# usb-debug.net
KiCad netlist of a schematic drawn in Altium Designer
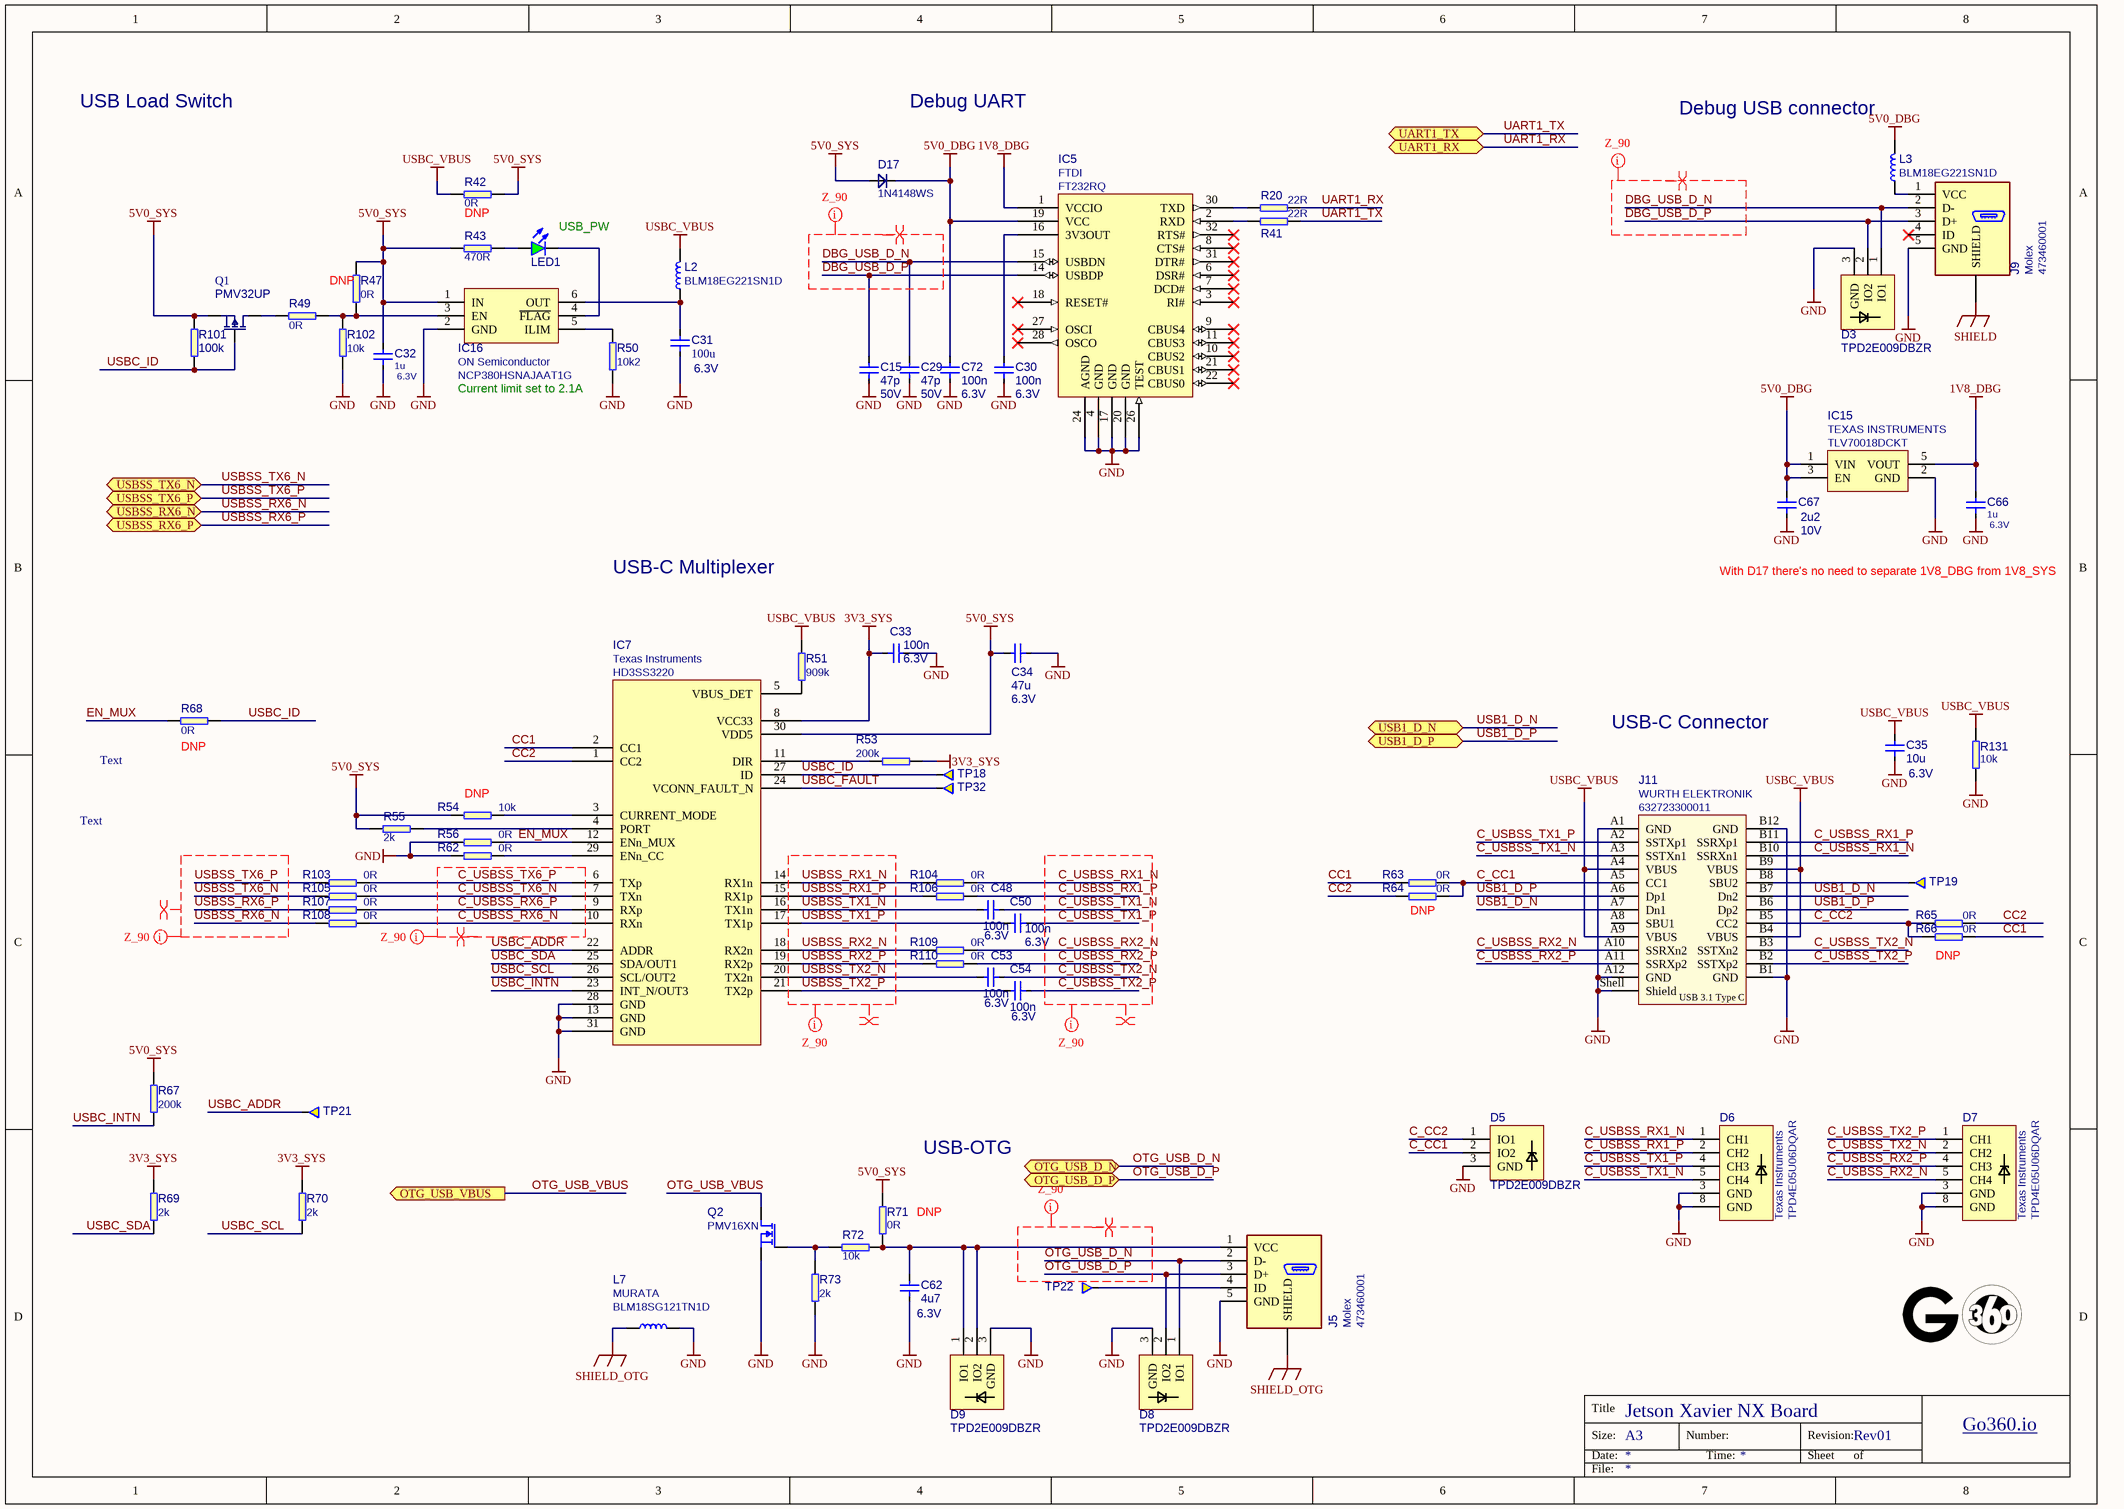
[diagram p0: usb-debug.SchDoc]

(export (version "E")
  (design (tool "Eeschema 10.0.6"))
  (components
    (comp (ref "C15")
      (value "47p")
      (footprint "0402")
      (description "MLCC SMT Capacitor 47pF 0402")
      (fields
        (field (name "PARTNUMBER") "C_47p_0402")
        (field (name "MANUFACTURER") "KEMET")
        (field (name "VOLTAGE") "50V")
      )
      (libsource (lib "jetson-nano-baseboard") (part "C_47p_0402"))
    )
    (comp (ref "C29")
      (value "47p")
      (footprint "0402")
      (description "MLCC SMT Capacitor 47pF 0402")
      (fields
        (field (name "PARTNUMBER") "C_47p_0402")
        (field (name "MANUFACTURER") "KEMET")
        (field (name "VOLTAGE") "50V")
      )
      (libsource (lib "jetson-nano-baseboard") (part "C_47p_0402"))
    )
    (comp (ref "C30")
      (value "100n")
      (footprint "0402")
      (description "MLCC SMT Capacitor 100n 0402")
      (fields
        (field (name "MANUFACTURER") "TDK")
        (field (name "PARTNUMBER") "C_100n_0402")
        (field (name "VOLTAGE") "6.3V")
      )
      (libsource (lib "jetson-nano-baseboard") (part "C_100n_0402"))
    )
    (comp (ref "C31")
      (value "100u")
      (footprint "1206")
      (description "MLCC SMT Capacitor 100uF 1206")
      (fields
        (field (name "PARTNUMBER") "C_100u_1206")
        (field (name "MANUFACTURER") "KEMET")
        (field (name "VOLTAGE") "6.3V")
      )
      (libsource (lib "jetson-nano-baseboard") (part "C_100u_1206"))
    )
    (comp (ref "C32")
      (value "1u")
      (footprint "0402")
      (description "MLCC SMT Capacitor 1uF 0402")
      (fields
        (field (name "PARTNUMBER") "C_1u_0402")
        (field (name "MANUFACTURER") "MULTICOMP")
        (field (name "VOLTAGE") "6.3V")
      )
      (libsource (lib "jetson-nano-baseboard") (part "C_1u_0402"))
    )
    (comp (ref "C33")
      (value "100n")
      (footprint "0402")
      (description "MLCC SMT Capacitor 100n 0402")
      (fields
        (field (name "MANUFACTURER") "TDK")
        (field (name "PARTNUMBER") "C_100n_0402")
        (field (name "VOLTAGE") "6.3V")
      )
      (libsource (lib "jetson-nano-baseboard") (part "C_100n_0402"))
    )
    (comp (ref "C34")
      (value "47u")
      (footprint "0805")
      (description "MLCC SMT Capacitor 47uF 0805")
      (fields
        (field (name "PARTNUMBER") "C_47u_0805")
        (field (name "MANUFACTURER") "KEMET")
        (field (name "VOLTAGE") "6.3V")
      )
      (libsource (lib "jetson-nano-baseboard") (part "C_47u_0805"))
    )
    (comp (ref "C35")
      (value "10u")
      (footprint "0603")
      (description "MLCC SMT Capacitor 10uF 0603")
      (fields
        (field (name "PARTNUMBER") "C_10u_0603")
        (field (name "MANUFACTURER") "Walsin")
        (field (name "VOLTAGE") "6.3V")
      )
      (libsource (lib "jetson-nano-baseboard") (part "C_10u_0603"))
    )
    (comp (ref "C48")
      (value "100n")
      (footprint "0402")
      (description "MLCC SMT Capacitor 100n 0402")
      (fields
        (field (name "MANUFACTURER") "TDK")
        (field (name "PARTNUMBER") "C_100n_0402")
        (field (name "VOLTAGE") "6.3V")
      )
      (libsource (lib "jetson-nano-baseboard") (part "C_100n_0402"))
    )
    (comp (ref "C50")
      (value "100n")
      (footprint "0402")
      (description "MLCC SMT Capacitor 100n 0402")
      (fields
        (field (name "MANUFACTURER") "TDK")
        (field (name "PARTNUMBER") "C_100n_0402")
        (field (name "VOLTAGE") "6.3V")
      )
      (libsource (lib "jetson-nano-baseboard") (part "C_100n_0402"))
    )
    (comp (ref "C53")
      (value "100n")
      (footprint "0402")
      (description "MLCC SMT Capacitor 100n 0402")
      (fields
        (field (name "MANUFACTURER") "TDK")
        (field (name "PARTNUMBER") "C_100n_0402")
        (field (name "VOLTAGE") "6.3V")
      )
      (libsource (lib "jetson-nano-baseboard") (part "C_100n_0402"))
    )
    (comp (ref "C54")
      (value "100n")
      (footprint "0402")
      (description "MLCC SMT Capacitor 100n 0402")
      (fields
        (field (name "MANUFACTURER") "TDK")
        (field (name "PARTNUMBER") "C_100n_0402")
        (field (name "VOLTAGE") "6.3V")
      )
      (libsource (lib "jetson-nano-baseboard") (part "C_100n_0402"))
    )
    (comp (ref "C62")
      (value "4u7")
      (footprint "0402")
      (description "MLCC SMT Capacitor 4.7uF 0402")
      (fields
        (field (name "PARTNUMBER") "C_4u7_0402")
        (field (name "MANUFACTURER") "MURATA")
        (field (name "VOLTAGE") "6.3V")
      )
      (libsource (lib "jetson-nano-baseboard") (part "C_4u7_0402"))
    )
    (comp (ref "C66")
      (value "1u")
      (footprint "0402")
      (description "MLCC SMT Capacitor 1uF 0402")
      (fields
        (field (name "PARTNUMBER") "C_1u_0402")
        (field (name "MANUFACTURER") "MULTICOMP")
        (field (name "VOLTAGE") "6.3V")
      )
      (libsource (lib "jetson-nano-baseboard") (part "C_1u_0402"))
    )
    (comp (ref "C67")
      (value "2u2")
      (footprint "0402")
      (description "MLCC SMT Capacitor 2.2uF 0402")
      (fields
        (field (name "MANUFACTURER") "TDK")
        (field (name "PARTNUMBER") "C_2u2_0402")
        (field (name "VOLTAGE") "10V")
      )
      (libsource (lib "jetson-nano-baseboard") (part "C_2u2_0402"))
    )
    (comp (ref "C72")
      (value "100n")
      (footprint "0402")
      (description "MLCC SMT Capacitor 100n 0402")
      (fields
        (field (name "MANUFACTURER") "TDK")
        (field (name "PARTNUMBER") "C_100n_0402")
        (field (name "VOLTAGE") "6.3V")
      )
      (libsource (lib "jetson-nano-baseboard") (part "C_100n_0402"))
    )
    (comp (ref "D3")
      (value "TPD2E009DBZR")
      (footprint "SOT-23")
      (description "DIODE, SCHOTTKY, 30V, 200MA, SOT-23")
      (fields (field (name "MANUFACTURER") "NXP"))
      (libsource (lib "jetson-nano-baseboard") (part "TPD2E009DBZR"))
    )
    (comp (ref "D5")
      (value "TPD2E009DBZR")
      (footprint "SOT-23")
      (description "DIODE, SCHOTTKY, 30V, 200MA, SOT-23")
      (fields (field (name "MANUFACTURER") "NXP"))
      (libsource (lib "") (part "TPD2E009DBZR_2"))
    )
    (comp (ref "D6")
      (value "TPD4E05U06")
      (footprint "TPD4E05U06_PASS")
      (description "ESD Suppressors 4-CH")
      (fields
        (field (name "PARTNUMBER") "TPD4E05U06_PASS")
        (field (name "MANUFACTURER") "Texas Instruments")
        (field (name "PARTSYMBOL") "TPD4E05U06DQAR")
      )
      (libsource (lib "jetson-nano-baseboard") (part "TPD4E05U06"))
    )
    (comp (ref "D7")
      (value "TPD4E05U06")
      (footprint "TPD4E05U06_PASS")
      (description "ESD Suppressors 4-CH")
      (fields
        (field (name "PARTNUMBER") "TPD4E05U06_PASS")
        (field (name "MANUFACTURER") "Texas Instruments")
        (field (name "PARTSYMBOL") "TPD4E05U06DQAR")
      )
      (libsource (lib "jetson-nano-baseboard") (part "TPD4E05U06"))
    )
    (comp (ref "D8")
      (value "TPD2E009DBZR")
      (footprint "SOT-23s")
      (description "DIODE, SCHOTTKY, 30V, 200MA, SOT-23")
      (fields (field (name "MANUFACTURER") "NXP"))
      (libsource (lib "jetson-nano-baseboard") (part "TPD2E009DBZR"))
    )
    (comp (ref "D9")
      (value "TPD2E009DBZR")
      (footprint "SOT-23s")
      (description "DIODE, SCHOTTKY, 30V, 200MA, SOT-23")
      (fields (field (name "MANUFACTURER") "NXP"))
      (libsource (lib "") (part "TPD2E009DBZR_1"))
    )
    (comp (ref "D17")
      (value "1N4148WS")
      (footprint "SOD-323")
      (description "Diode small signal")
      (fields (field (name "MANUFACTURER") "ON SEMICONDUCTOR"))
      (libsource (lib "jetson-nano-baseboard") (part "diode"))
    )
    (comp (ref "IC5")
      (value "FT232RQ")
      (footprint "QFN-32")
      (description "USB to serial UART interface")
      (fields (field (name "MANUFACTURER") "FTDI") (field (name "PARTNUMBER") "FT232RQ"))
      (libsource (lib "jetson-nano-baseboard") (part "FT232RQ"))
    )
    (comp (ref "IC7")
      (value "HD3SS3220")
      (footprint "RNH0030A")
      (description "IC DRP PORT CTLR USB-C 30WQFN")
      (fields (field (name "MANUFACTURER") "Texas Instruments"))
      (libsource (lib "jetson-nano-baseboard") (part "HD3SS3220"))
    )
    (comp (ref "IC15")
      (value "TLV70018DCKT")
      (footprint "SC70-5")
      (description "Voltage Regulator, 2V to 5.5V, 175mV Dropout, 1.8Vout, 200mAout")
      (fields (field (name "MANUFACTURER") "TEXAS INSTRUMENTS"))
      (libsource (lib "jetson-nano-baseboard") (part "TLV700"))
    )
    (comp (ref "IC16")
      (value "NCP380HSNAJAAT1G")
      (footprint "TSOP-6")
      (description "POWER LOAD SWITCH, HIGH SIDE")
      (fields (field (name "MANUFACTURER") "ON Semiconductor"))
      (libsource (lib "jetson-nano-baseboard") (part "NCP380HSNAJAAT1G"))
    )
    (comp (ref "J5")
      (value "Molex 47346-0001")
      (footprint "CON-Molex-047346-0001")
      (description "USB - micro B Receptacle Connector 5 Position Surface Mount, Right Angle, Horizontal")
      (fields
        (field (name "PARTNUMBER") "CON-Molex-47346-0001")
        (field (name "MANUFACTURER") "Molex")
        (field (name "PARTSYMBOL") "473460001")
      )
      (libsource (lib "jetson-nano-baseboard") (part "Micro USB B"))
    )
    (comp (ref "J9")
      (value "Molex 47346-0001")
      (footprint "CON-Molex-047346-0001")
      (description "USB - micro B Receptacle Connector 5 Position Surface Mount, Right Angle, Horizontal")
      (fields
        (field (name "PARTNUMBER") "CON-Molex-47346-0001")
        (field (name "MANUFACTURER") "Molex")
        (field (name "PARTSYMBOL") "473460001")
      )
      (libsource (lib "jetson-nano-baseboard") (part "Micro USB B"))
    )
    (comp (ref "J11")
      (value "632723300011")
      (footprint "WE_632723300011")
      (description "USB 3.1 Type C Receptacle Horizontal THR WR-COM")
      (fields (field (name "PARTNUMBER") "WE_632723300011") (field (name "MANUFACTURER") "WURTH ELEKTRONIK"))
      (libsource (lib "jetson-nano-baseboard") (part "WE_632723300011"))
    )
    (comp (ref "L2")
      (value "BLM18EG221SN1D")
      (footprint "0603")
      (description "MURATA  BLM18EG221SN1D  FERRITE BEAD, 0.05OHM, 2A, 0603")
      (fields (field (name "MANUFACTURER") "MURATA"))
      (libsource (lib "jetson-nano-baseboard") (part "BLM18EG221SN1D"))
    )
    (comp (ref "L3")
      (value "BLM18EG221SN1D")
      (footprint "0603")
      (description "MURATA  BLM18EG221SN1D  FERRITE BEAD, 0.05OHM, 2A, 0603")
      (fields (field (name "MANUFACTURER") "MURATA"))
      (libsource (lib "jetson-nano-baseboard") (part "BLM18EG221SN1D"))
    )
    (comp (ref "L7")
      (value "BLM18SG121TN1D")
      (footprint "0603")
      (description "FERRITE BEAD, 0.025OHM, 3A, 0603")
      (fields (field (name "MANUFACTURER") "MURATA"))
      (libsource (lib "jetson-nano-baseboard") (part "BLM18SG121TN1D"))
    )
    (comp (ref "LED1")
      (value "KPT-1608SGC")
      (footprint "LED0603")
      (description "LED Green 0603 case")
      (fields (field (name "MANUFACTURER") "KINGBRIGHT") (field (name "PARTNUMBER") "LED_G"))
      (libsource (lib "jetson-nano-baseboard") (part "LED"))
    )
    (comp (ref "Q1")
      (value "PMV32UP")
      (footprint "SOT-23s")
      (description "P CH, 20V, 4A")
      (fields (field (name "MANUFACTURER") "NXP"))
      (libsource (lib "jetson-nano-baseboard") (part "PMOS"))
    )
    (comp (ref "Q2")
      (value "PMV16XN")
      (footprint "SOT-23s")
      (description "MOSFET, N CH")
      (fields (field (name "MANUFACTURER") "NXP"))
      (libsource (lib "jetson-nano-baseboard") (part "NMOS_PMV16XN"))
    )
    (comp (ref "R20")
      (value "22R")
      (footprint "0402")
      (description "RES, 22R, 0402")
      (fields (field (name "MANUFACTURER") "VISHAY") (field (name "PARTNUMBER") "R_22R_0402"))
      (libsource (lib "jetson-nano-baseboard") (part "R_22R_0402"))
    )
    (comp (ref "R41")
      (value "22R")
      (footprint "0402")
      (description "RES, 22R, 0402")
      (fields (field (name "MANUFACTURER") "VISHAY") (field (name "PARTNUMBER") "R_22R_0402"))
      (libsource (lib "jetson-nano-baseboard") (part "R_22R_0402"))
    )
    (comp (ref "R42")
      (value "0R")
      (footprint "0402")
      (description "RES, 0R, 0402")
      (fields (field (name "PARTNUMBER") "R_0R_0402") (field (name "MANUFACTURER") "Panasonic"))
      (libsource (lib "") (part "R_0R_0402_2"))
    )
    (comp (ref "R43")
      (value "470R")
      (footprint "0402")
      (description "RES, 470R, 0402")
      (fields (field (name "PARTNUMBER") "R_470R_0402") (field (name "MANUFACTURER") "VISHAY"))
      (libsource (lib "jetson-nano-baseboard") (part "R_470R_0402"))
    )
    (comp (ref "R47")
      (value "0R")
      (footprint "0402")
      (description "RES, 0R, 0402")
      (fields (field (name "PARTNUMBER") "R_0R_0402") (field (name "MANUFACTURER") "Panasonic"))
      (libsource (lib "") (part "R_0R_0402_1"))
    )
    (comp (ref "R49")
      (value "0R")
      (footprint "0402")
      (description "RES, 0R, 0402")
      (fields (field (name "PARTNUMBER") "R_0R_0402") (field (name "MANUFACTURER") "Panasonic"))
      (libsource (lib "jetson-nano-baseboard") (part "R_0R_0402"))
    )
    (comp (ref "R50")
      (value "10k2")
      (footprint "0402")
      (description "RES, 10k2, 0402, 0.1%")
      (fields (field (name "PARTNUMBER") "R_10k2_0402_0.1%") (field (name "MANUFACTURER") "TE CONECTIVITY"))
      (libsource (lib "jetson-nano-baseboard") (part "R_10k2_0402"))
    )
    (comp (ref "R51")
      (value "909k")
      (footprint "0402")
      (description "RES, 909k, 0402")
      (fields (field (name "PARTNUMBER") "R_909k_0402") (field (name "MANUFACTURER") "Panasonic"))
      (libsource (lib "jetson-nano-baseboard") (part "R_909k_0402"))
    )
    (comp (ref "R53")
      (value "200k")
      (footprint "0402")
      (description "RES, 200k, 0402")
      (fields (field (name "PARTNUMBER") "R_200k_0402") (field (name "MANUFACTURER") "YAGEO"))
      (libsource (lib "jetson-nano-baseboard") (part "R_200k_0402"))
    )
    (comp (ref "R54")
      (value "10k")
      (footprint "0402")
      (description "RES, 10k, 0402")
      (fields (field (name "PARTNUMBER") "R_10k_0402") (field (name "MANUFACTURER") "MULTICOMP"))
      (libsource (lib "jetson-nano-baseboard") (part "R_10k_0402"))
    )
    (comp (ref "R55")
      (value "2k")
      (footprint "0402")
      (description "RES, 2k, 0402")
      (fields (field (name "PARTNUMBER") "R_2k_0402") (field (name "MANUFACTURER") "VISHAY"))
      (libsource (lib "") (part "R_2k_0402_1"))
    )
    (comp (ref "R56")
      (value "0R")
      (footprint "0402")
      (description "RES, 0R, 0402")
      (fields (field (name "PARTNUMBER") "R_0R_0402") (field (name "MANUFACTURER") "Panasonic"))
      (libsource (lib "jetson-nano-baseboard") (part "R_0R_0402"))
    )
    (comp (ref "R62")
      (value "0R")
      (footprint "0402")
      (description "RES, 0R, 0402")
      (fields (field (name "PARTNUMBER") "R_0R_0402") (field (name "MANUFACTURER") "Panasonic"))
      (libsource (lib "jetson-nano-baseboard") (part "R_0R_0402"))
    )
    (comp (ref "R63")
      (value "0R")
      (footprint "0402")
      (description "RES, 0R, 0402")
      (fields (field (name "PARTNUMBER") "R_0R_0402") (field (name "MANUFACTURER") "Panasonic"))
      (libsource (lib "jetson-nano-baseboard") (part "R_0R_0402"))
    )
    (comp (ref "R64")
      (value "0R")
      (footprint "0402")
      (description "RES, 0R, 0402")
      (fields (field (name "PARTNUMBER") "R_0R_0402") (field (name "MANUFACTURER") "Panasonic"))
      (libsource (lib "jetson-nano-baseboard") (part "R_0R_0402"))
    )
    (comp (ref "R65")
      (value "0R")
      (footprint "0402")
      (description "RES, 0R, 0402")
      (fields (field (name "PARTNUMBER") "R_0R_0402") (field (name "MANUFACTURER") "Panasonic"))
      (libsource (lib "jetson-nano-baseboard") (part "R_0R_0402"))
    )
    (comp (ref "R66")
      (value "0R")
      (footprint "0402")
      (description "RES, 0R, 0402")
      (fields (field (name "PARTNUMBER") "R_0R_0402") (field (name "MANUFACTURER") "Panasonic"))
      (libsource (lib "jetson-nano-baseboard") (part "R_0R_0402"))
    )
    (comp (ref "R67")
      (value "200k")
      (footprint "0402")
      (description "RES, 200k, 0402")
      (fields (field (name "PARTNUMBER") "R_200k_0402") (field (name "MANUFACTURER") "YAGEO"))
      (libsource (lib "") (part "R_200k_0402_1"))
    )
    (comp (ref "R68")
      (value "0R")
      (footprint "0402")
      (description "RES, 0R, 0402")
      (fields (field (name "PARTNUMBER") "R_0R_0402") (field (name "MANUFACTURER") "Panasonic"))
      (libsource (lib "jetson-nano-baseboard") (part "R_0R_0402"))
    )
    (comp (ref "R69")
      (value "2k")
      (footprint "0402")
      (description "RES, 2k, 0402")
      (fields (field (name "PARTNUMBER") "R_2k_0402") (field (name "MANUFACTURER") "VISHAY"))
      (libsource (lib "jetson-nano-baseboard") (part "R_2k_0402"))
    )
    (comp (ref "R70")
      (value "2k")
      (footprint "0402")
      (description "RES, 2k, 0402")
      (fields (field (name "PARTNUMBER") "R_2k_0402") (field (name "MANUFACTURER") "VISHAY"))
      (libsource (lib "jetson-nano-baseboard") (part "R_2k_0402"))
    )
    (comp (ref "R71")
      (value "0R")
      (footprint "0402")
      (description "RES, 0R, 0402")
      (fields (field (name "PARTNUMBER") "R_0R_0402") (field (name "MANUFACTURER") "Panasonic"))
      (libsource (lib "jetson-nano-baseboard") (part "R_0R_0402"))
    )
    (comp (ref "R72")
      (value "10k")
      (footprint "0402")
      (description "RES, 10k, 0402")
      (fields (field (name "PARTNUMBER") "R_10k_0402") (field (name "MANUFACTURER") "MULTICOMP"))
      (libsource (lib "") (part "R_10k_0402_2"))
    )
    (comp (ref "R73")
      (value "2k")
      (footprint "0402")
      (description "RES, 2k, 0402")
      (fields (field (name "PARTNUMBER") "R_2k_0402") (field (name "MANUFACTURER") "VISHAY"))
      (libsource (lib "jetson-nano-baseboard") (part "R_2k_0402"))
    )
    (comp (ref "R101")
      (value "100k")
      (footprint "0402")
      (description "SMT Resistor 100k 0402")
      (fields (field (name "PARTNUMBER") "R_100k_0402") (field (name "TOLERANCE") "1%"))
      (libsource (lib "jetson-nano-baseboard") (part "R_100k_0402"))
    )
    (comp (ref "R102")
      (value "10k")
      (footprint "0402")
      (description "RES, 10k, 0402")
      (fields (field (name "MANUFACTURER") "MULTICOMP") (field (name "PARTNUMBER") "R_10k_0402"))
      (libsource (lib "") (part "R_10k_0402_1"))
    )
    (comp (ref "R103")
      (value "0R")
      (footprint "0402")
      (description "RES, 0R, 0402")
      (fields (field (name "PARTNUMBER") "R_0R_0402") (field (name "MANUFACTURER") "Panasonic"))
      (libsource (lib "jetson-nano-baseboard") (part "R_0R_0402"))
    )
    (comp (ref "R104")
      (value "0R")
      (footprint "0402")
      (description "RES, 0R, 0402")
      (fields (field (name "PARTNUMBER") "R_0R_0402") (field (name "MANUFACTURER") "Panasonic"))
      (libsource (lib "jetson-nano-baseboard") (part "R_0R_0402"))
    )
    (comp (ref "R105")
      (value "0R")
      (footprint "0402")
      (description "RES, 0R, 0402")
      (fields (field (name "PARTNUMBER") "R_0R_0402") (field (name "MANUFACTURER") "Panasonic"))
      (libsource (lib "jetson-nano-baseboard") (part "R_0R_0402"))
    )
    (comp (ref "R106")
      (value "0R")
      (footprint "0402")
      (description "RES, 0R, 0402")
      (fields (field (name "PARTNUMBER") "R_0R_0402") (field (name "MANUFACTURER") "Panasonic"))
      (libsource (lib "jetson-nano-baseboard") (part "R_0R_0402"))
    )
    (comp (ref "R107")
      (value "0R")
      (footprint "0402")
      (description "RES, 0R, 0402")
      (fields (field (name "PARTNUMBER") "R_0R_0402") (field (name "MANUFACTURER") "Panasonic"))
      (libsource (lib "jetson-nano-baseboard") (part "R_0R_0402"))
    )
    (comp (ref "R108")
      (value "0R")
      (footprint "0402")
      (description "RES, 0R, 0402")
      (fields (field (name "PARTNUMBER") "R_0R_0402") (field (name "MANUFACTURER") "Panasonic"))
      (libsource (lib "jetson-nano-baseboard") (part "R_0R_0402"))
    )
    (comp (ref "R109")
      (value "0R")
      (footprint "0402")
      (description "RES, 0R, 0402")
      (fields (field (name "PARTNUMBER") "R_0R_0402") (field (name "MANUFACTURER") "Panasonic"))
      (libsource (lib "jetson-nano-baseboard") (part "R_0R_0402"))
    )
    (comp (ref "R110")
      (value "0R")
      (footprint "0402")
      (description "RES, 0R, 0402")
      (fields (field (name "PARTNUMBER") "R_0R_0402") (field (name "MANUFACTURER") "Panasonic"))
      (libsource (lib "jetson-nano-baseboard") (part "R_0R_0402"))
    )
    (comp (ref "R131")
      (value "10k")
      (footprint "0402")
      (description "RES, 10k, 0402")
      (fields (field (name "PARTNUMBER") "R_10k_0402") (field (name "MANUFACTURER") "MULTICOMP"))
      (libsource (lib "") (part "R_10k_0402_1"))
    )
    (comp (ref "TP18")
      (value "Testpad")
      (footprint "TP-R-1.5")
      (description "Testpad, round, 1.5mm")
      (fields (field (name "PARTNUMBER") "TP-R-1.5"))
      (libsource (lib "jetson-nano-baseboard") (part "Testpad"))
    )
    (comp (ref "TP19")
      (value "Testpad")
      (footprint "TP-R-1.5")
      (description "Testpad, round, 1.5mm")
      (fields (field (name "PARTNUMBER") "TP-R-1.5"))
      (libsource (lib "jetson-nano-baseboard") (part "Testpad"))
    )
    (comp (ref "TP21")
      (value "Testpad")
      (footprint "TP-R-1.5")
      (description "Testpad, round, 1.5mm")
      (fields (field (name "PARTNUMBER") "TP-R-1.5"))
      (libsource (lib "jetson-nano-baseboard") (part "Testpad"))
    )
    (comp (ref "TP22")
      (value "Testpad")
      (footprint "TP-R-1.5")
      (description "Testpad, round, 1.5mm")
      (fields (field (name "PARTNUMBER") "TP-R-1.5"))
      (libsource (lib "jetson-nano-baseboard") (part "Testpad"))
    )
    (comp (ref "TP32")
      (value "Testpad")
      (footprint "TP-R-1.5")
      (description "Testpad, round, 1.5mm")
      (fields (field (name "PARTNUMBER") "TP-R-1.5"))
      (libsource (lib "jetson-nano-baseboard") (part "Testpad"))
    )
  )
  (nets
    (net (code "1") (name "/CC1") (class "Default")
      (node (ref "IC7") (pin "2") (pinfunction "CC1_2") (pintype "passive"))
      (node (ref "R63") (pin "1") (pintype "passive"))
      (node (ref "R66") (pin "2") (pintype "passive"))
    )
    (net (code "2") (name "/CC2") (class "Default")
      (node (ref "IC7") (pin "1") (pinfunction "CC2_1") (pintype "passive"))
      (node (ref "R64") (pin "1") (pintype "passive"))
      (node (ref "R65") (pin "2") (pintype "passive"))
    )
    (net (code "3") (name "/C_CC1") (class "Default")
      (node (ref "D5") (pin "2") (pinfunction "IO2_2") (pintype "passive"))
      (node (ref "J11") (pin "A5") (pinfunction "CC1_A5") (pintype "passive"))
      (node (ref "R63") (pin "2") (pintype "passive"))
      (node (ref "R64") (pin "2") (pintype "passive"))
    )
    (net (code "4") (name "/C_CC2") (class "Default")
      (node (ref "D5") (pin "1") (pinfunction "IO1_1") (pintype "passive"))
      (node (ref "J11") (pin "B5") (pinfunction "CC2_B5") (pintype "passive"))
      (node (ref "R65") (pin "1") (pintype "passive"))
      (node (ref "R66") (pin "1") (pintype "passive"))
    )
    (net (code "5") (name "/C_USBSS_RX1_N") (class "Default")
      (node (ref "D6") (pin "1") (pinfunction "CH1_1") (pintype "passive"))
      (node (ref "J11") (pin "B10") (pinfunction "SSRXn1_B10") (pintype "passive"))
      (node (ref "R104") (pin "2") (pintype "passive"))
    )
    (net (code "6") (name "/C_USBSS_RX1_P") (class "Default")
      (node (ref "D6") (pin "2") (pinfunction "CH2_2") (pintype "passive"))
      (node (ref "J11") (pin "B11") (pinfunction "SSRXp1_B11") (pintype "passive"))
      (node (ref "R106") (pin "2") (pintype "passive"))
    )
    (net (code "7") (name "/C_USBSS_RX2_N") (class "Default")
      (node (ref "D7") (pin "5") (pinfunction "CH4_5") (pintype "passive"))
      (node (ref "J11") (pin "A10") (pinfunction "SSRXn2_A10") (pintype "passive"))
      (node (ref "R109") (pin "2") (pintype "passive"))
    )
    (net (code "8") (name "/C_USBSS_RX2_P") (class "Default")
      (node (ref "D7") (pin "4") (pinfunction "CH3_4") (pintype "passive"))
      (node (ref "J11") (pin "A11") (pinfunction "SSRXp2_A11") (pintype "passive"))
      (node (ref "R110") (pin "2") (pintype "passive"))
    )
    (net (code "9") (name "/C_USBSS_RX6_N") (class "Default")
      (node (ref "IC7") (pin "10") (pinfunction "RXn_10") (pintype "passive"))
      (node (ref "R108") (pin "2") (pintype "passive"))
    )
    (net (code "10") (name "/C_USBSS_RX6_P") (class "Default")
      (node (ref "IC7") (pin "9") (pinfunction "RXp_9") (pintype "passive"))
      (node (ref "R107") (pin "2") (pintype "passive"))
    )
    (net (code "11") (name "/C_USBSS_TX1_N") (class "Default")
      (node (ref "C48") (pin "1") (pinfunction "1_1") (pintype "passive"))
      (node (ref "D6") (pin "5") (pinfunction "CH4_5") (pintype "passive"))
      (node (ref "J11") (pin "A3") (pinfunction "SSTXn1_A3") (pintype "passive"))
    )
    (net (code "12") (name "/C_USBSS_TX1_P") (class "Default")
      (node (ref "C50") (pin "1") (pinfunction "1_1") (pintype "passive"))
      (node (ref "D6") (pin "4") (pinfunction "CH3_4") (pintype "passive"))
      (node (ref "J11") (pin "A2") (pinfunction "SSTXp1_A2") (pintype "passive"))
    )
    (net (code "13") (name "/C_USBSS_TX2_N") (class "Default")
      (node (ref "C53") (pin "1") (pinfunction "1_1") (pintype "passive"))
      (node (ref "D7") (pin "2") (pinfunction "CH2_2") (pintype "passive"))
      (node (ref "J11") (pin "B3") (pinfunction "SSTXn2_B3") (pintype "passive"))
    )
    (net (code "14") (name "/C_USBSS_TX2_P") (class "Default")
      (node (ref "C54") (pin "1") (pinfunction "1_1") (pintype "passive"))
      (node (ref "D7") (pin "1") (pinfunction "CH1_1") (pintype "passive"))
      (node (ref "J11") (pin "B2") (pinfunction "SSTXp2_B2") (pintype "passive"))
    )
    (net (code "15") (name "/C_USBSS_TX6_N") (class "Default")
      (node (ref "IC7") (pin "7") (pinfunction "TXn_7") (pintype "passive"))
      (node (ref "R105") (pin "2") (pintype "passive"))
    )
    (net (code "16") (name "/C_USBSS_TX6_P") (class "Default")
      (node (ref "IC7") (pin "6") (pinfunction "TXp_6") (pintype "passive"))
      (node (ref "R103") (pin "2") (pintype "passive"))
    )
    (net (code "17") (name "/DBG_USB_D_N") (class "Default")
      (node (ref "C29") (pin "2") (pinfunction "2_2") (pintype "passive"))
      (node (ref "D3") (pin "1") (pinfunction "IO1_1") (pintype "passive"))
      (node (ref "IC5") (pin "15") (pinfunction "USBDN_15") (pintype "bidirectional"))
      (node (ref "J9") (pin "2") (pinfunction "D-_2") (pintype "passive"))
    )
    (net (code "18") (name "/DBG_USB_D_P") (class "Default")
      (node (ref "C15") (pin "2") (pinfunction "2_2") (pintype "passive"))
      (node (ref "D3") (pin "2") (pinfunction "IO2_2") (pintype "passive"))
      (node (ref "IC5") (pin "14") (pinfunction "USBDP_14") (pintype "bidirectional"))
      (node (ref "J9") (pin "3") (pinfunction "D+_3") (pintype "passive"))
    )
    (net (code "19") (name "/EN_MUX") (class "Default")
      (node (ref "IC7") (pin "12") (pinfunction "ENn_MUX_12") (pintype "passive"))
      (node (ref "R56") (pin "2") (pintype "passive"))
      (node (ref "R68") (pin "1") (pintype "passive"))
    )
    (net (code "20") (name "/OTG_USB_D_N") (class "Default")
      (node (ref "D8") (pin "1") (pinfunction "IO1_1") (pintype "passive"))
      (node (ref "J5") (pin "2") (pinfunction "D-_2") (pintype "passive"))
    )
    (net (code "21") (name "/OTG_USB_D_P") (class "Default")
      (node (ref "D8") (pin "2") (pinfunction "IO2_2") (pintype "passive"))
      (node (ref "J5") (pin "3") (pinfunction "D+_3") (pintype "passive"))
    )
    (net (code "22") (name "/OTG_USB_VBUS") (class "Default")
      (node (ref "Q2") (pin "3") (pinfunction "D_3") (pintype "passive"))
    )
    (net (code "23") (name "/UART1_RX") (class "Default") (node (ref "R20") (pin "2") (pintype "passive")))
    (net (code "24") (name "/UART1_TX") (class "Default") (node (ref "R41") (pin "2") (pintype "passive")))
    (net (code "25") (name "/USB1_D_N") (class "Default")
      (node (ref "J11") (pin "A7") (pinfunction "Dn1_A7") (pintype "passive"))
      (node (ref "J11") (pin "B7") (pinfunction "Dn2_B7") (pintype "passive"))
    )
    (net (code "26") (name "/USB1_D_P") (class "Default")
      (node (ref "J11") (pin "A6") (pinfunction "Dp1_A6") (pintype "passive"))
      (node (ref "J11") (pin "B6") (pinfunction "Dp2_B6") (pintype "passive"))
    )
    (net (code "27") (name "/USBC_ADDR") (class "Default")
      (node (ref "IC7") (pin "22") (pinfunction "ADDR_22") (pintype "passive"))
      (node (ref "TP21") (pin "1") (pintype "passive"))
    )
    (net (code "28") (name "/USBC_FAULT") (class "Default")
      (node (ref "IC7") (pin "24") (pinfunction "VCONN_FAULT_N_24") (pintype "passive"))
      (node (ref "TP32") (pin "1") (pintype "passive"))
    )
    (net (code "29") (name "/USBC_ID") (class "Default")
      (node (ref "IC7") (pin "27") (pinfunction "ID_27") (pintype "passive"))
      (node (ref "Q1") (pin "1") (pinfunction "G_1") (pintype "passive"))
      (node (ref "R101") (pin "1") (pintype "passive"))
      (node (ref "R68") (pin "2") (pintype "passive"))
      (node (ref "TP18") (pin "1") (pintype "passive"))
    )
    (net (code "30") (name "/USBC_INTN") (class "Default")
      (node (ref "IC7") (pin "23") (pinfunction "INT_N/OUT3_23") (pintype "passive"))
      (node (ref "R67") (pin "1") (pintype "passive"))
    )
    (net (code "31") (name "/USBC_SCL") (class "Default")
      (node (ref "IC7") (pin "26") (pinfunction "SCL/OUT2_26") (pintype "passive"))
      (node (ref "R70") (pin "2") (pintype "passive"))
    )
    (net (code "32") (name "/USBC_SDA") (class "Default")
      (node (ref "IC7") (pin "25") (pinfunction "SDA/OUT1_25") (pintype "passive"))
      (node (ref "R69") (pin "2") (pintype "passive"))
    )
    (net (code "33") (name "/USBSS_RX1_N") (class "Default")
      (node (ref "IC7") (pin "14") (pinfunction "RX1n_14") (pintype "passive"))
      (node (ref "R104") (pin "1") (pintype "passive"))
    )
    (net (code "34") (name "/USBSS_RX1_P") (class "Default")
      (node (ref "IC7") (pin "15") (pinfunction "RX1p_15") (pintype "passive"))
      (node (ref "R106") (pin "1") (pintype "passive"))
    )
    (net (code "35") (name "/USBSS_RX2_N") (class "Default")
      (node (ref "IC7") (pin "18") (pinfunction "RX2n_18") (pintype "passive"))
      (node (ref "R109") (pin "1") (pintype "passive"))
    )
    (net (code "36") (name "/USBSS_RX2_P") (class "Default")
      (node (ref "IC7") (pin "19") (pinfunction "RX2p_19") (pintype "passive"))
      (node (ref "R110") (pin "1") (pintype "passive"))
    )
    (net (code "37") (name "/USBSS_RX6_N") (class "Default")
      (node (ref "R108") (pin "1") (pintype "passive"))
    )
    (net (code "38") (name "/USBSS_RX6_P") (class "Default")
      (node (ref "R107") (pin "1") (pintype "passive"))
    )
    (net (code "39") (name "/USBSS_TX1_N") (class "Default")
      (node (ref "C48") (pin "2") (pinfunction "2_2") (pintype "passive"))
      (node (ref "IC7") (pin "16") (pinfunction "TX1n_16") (pintype "passive"))
    )
    (net (code "40") (name "/USBSS_TX1_P") (class "Default")
      (node (ref "C50") (pin "2") (pinfunction "2_2") (pintype "passive"))
      (node (ref "IC7") (pin "17") (pinfunction "TX1p_17") (pintype "passive"))
    )
    (net (code "41") (name "/USBSS_TX2_N") (class "Default")
      (node (ref "C53") (pin "2") (pinfunction "2_2") (pintype "passive"))
      (node (ref "IC7") (pin "20") (pinfunction "TX2n_20") (pintype "passive"))
    )
    (net (code "42") (name "/USBSS_TX2_P") (class "Default")
      (node (ref "C54") (pin "2") (pinfunction "2_2") (pintype "passive"))
      (node (ref "IC7") (pin "21") (pinfunction "TX2p_21") (pintype "passive"))
    )
    (net (code "43") (name "/USBSS_TX6_N") (class "Default")
      (node (ref "R105") (pin "1") (pintype "passive"))
    )
    (net (code "44") (name "/USBSS_TX6_P") (class "Default")
      (node (ref "R103") (pin "1") (pintype "passive"))
    )
    (net (code "45") (name "1V8_DBG") (class "Default")
      (node (ref "C66") (pin "2") (pinfunction "2_2") (pintype "passive"))
      (node (ref "IC15") (pin "5") (pinfunction "VOUT_5") (pintype "passive"))
      (node (ref "IC5") (pin "1") (pinfunction "VCCIO_1") (pintype "power_in"))
    )
    (net (code "46") (name "3V3_SYS") (class "Default")
      (node (ref "C33") (pin "1") (pinfunction "1_1") (pintype "passive"))
      (node (ref "IC7") (pin "8") (pinfunction "VCC33_8") (pintype "passive"))
      (node (ref "R53") (pin "2") (pintype "passive"))
      (node (ref "R69") (pin "1") (pintype "passive"))
      (node (ref "R70") (pin "1") (pintype "passive"))
    )
    (net (code "47") (name "5V0_DBG") (class "Default")
      (node (ref "C67") (pin "2") (pinfunction "2_2") (pintype "passive"))
      (node (ref "C72") (pin "2") (pinfunction "2_2") (pintype "passive"))
      (node (ref "D17") (pin "C") (pinfunction "C_C") (pintype "passive"))
      (node (ref "IC15") (pin "1") (pinfunction "VIN_1") (pintype "passive"))
      (node (ref "IC15") (pin "3") (pinfunction "EN_3") (pintype "passive"))
      (node (ref "IC5") (pin "19") (pinfunction "VCC_19") (pintype "power_in"))
      (node (ref "L3") (pin "2") (pintype "passive"))
    )
    (net (code "48") (name "5V0_SYS") (class "Default")
      (node (ref "C32") (pin "2") (pinfunction "2_2") (pintype "passive"))
      (node (ref "C34") (pin "2") (pinfunction "2_2") (pintype "passive"))
      (node (ref "D17") (pin "A") (pinfunction "A_A") (pintype "passive"))
      (node (ref "IC16") (pin "1") (pinfunction "IN_1") (pintype "passive"))
      (node (ref "IC7") (pin "30") (pinfunction "VDD5_30") (pintype "passive"))
      (node (ref "Q1") (pin "2") (pinfunction "S_2") (pintype "passive"))
      (node (ref "R101") (pin "2") (pintype "passive"))
      (node (ref "R42") (pin "1") (pintype "passive"))
      (node (ref "R43") (pin "2") (pintype "passive"))
      (node (ref "R47") (pin "2") (pintype "passive"))
      (node (ref "R54") (pin "1") (pintype "passive"))
      (node (ref "R55") (pin "1") (pintype "passive"))
      (node (ref "R67") (pin "2") (pintype "passive"))
      (node (ref "R71") (pin "2") (pintype "passive"))
    )
    (net (code "49") (name "GND") (class "Default")
      (node (ref "C15") (pin "1") (pinfunction "1_1") (pintype "passive"))
      (node (ref "C29") (pin "1") (pinfunction "1_1") (pintype "passive"))
      (node (ref "C30") (pin "1") (pinfunction "1_1") (pintype "passive"))
      (node (ref "C31") (pin "1") (pinfunction "1_1") (pintype "passive"))
      (node (ref "C32") (pin "1") (pinfunction "1_1") (pintype "passive"))
      (node (ref "C33") (pin "2") (pinfunction "2_2") (pintype "passive"))
      (node (ref "C34") (pin "1") (pinfunction "1_1") (pintype "passive"))
      (node (ref "C35") (pin "1") (pinfunction "1_1") (pintype "passive"))
      (node (ref "C62") (pin "1") (pinfunction "1_1") (pintype "passive"))
      (node (ref "C66") (pin "1") (pinfunction "1_1") (pintype "passive"))
      (node (ref "C67") (pin "1") (pinfunction "1_1") (pintype "passive"))
      (node (ref "C72") (pin "1") (pinfunction "1_1") (pintype "passive"))
      (node (ref "D3") (pin "3") (pinfunction "GND_3") (pintype "passive"))
      (node (ref "D5") (pin "3") (pinfunction "GND_3") (pintype "passive"))
      (node (ref "D6") (pin "3") (pinfunction "GND_3") (pintype "passive"))
      (node (ref "D6") (pin "8") (pinfunction "GND_8") (pintype "passive"))
      (node (ref "D7") (pin "3") (pinfunction "GND_3") (pintype "passive"))
      (node (ref "D7") (pin "8") (pinfunction "GND_8") (pintype "passive"))
      (node (ref "D8") (pin "3") (pinfunction "GND_3") (pintype "passive"))
      (node (ref "D9") (pin "3") (pinfunction "GND_3") (pintype "passive"))
      (node (ref "IC15") (pin "2") (pinfunction "GND_2") (pintype "passive"))
      (node (ref "IC16") (pin "2") (pinfunction "GND_2") (pintype "passive"))
      (node (ref "IC5") (pin "17") (pinfunction "GND_17") (pintype "power_in"))
      (node (ref "IC5") (pin "20") (pinfunction "GND_20") (pintype "power_in"))
      (node (ref "IC5") (pin "24") (pinfunction "AGND_24") (pintype "power_in"))
      (node (ref "IC5") (pin "26") (pinfunction "TEST_26") (pintype "input"))
      (node (ref "IC5") (pin "4") (pinfunction "GND_4") (pintype "power_in"))
      (node (ref "IC7") (pin "13") (pinfunction "GND_13") (pintype "passive"))
      (node (ref "IC7") (pin "28") (pinfunction "GND_28") (pintype "passive"))
      (node (ref "IC7") (pin "31") (pinfunction "GND_31") (pintype "passive"))
      (node (ref "J11") (pin "A1") (pinfunction "GND_A1") (pintype "passive"))
      (node (ref "J11") (pin "A12") (pinfunction "GND_A12") (pintype "passive"))
      (node (ref "J11") (pin "B1") (pinfunction "GND_B1") (pintype "passive"))
      (node (ref "J11") (pin "B12") (pinfunction "GND_B12") (pintype "passive"))
      (node (ref "J11") (pin "Shell") (pinfunction "Shield_Shell") (pintype "passive"))
      (node (ref "J5") (pin "5") (pinfunction "GND_5") (pintype "power_in"))
      (node (ref "J9") (pin "5") (pinfunction "GND_5") (pintype "power_in"))
      (node (ref "L7") (pin "2") (pintype "passive"))
      (node (ref "Q2") (pin "2") (pinfunction "S_2") (pintype "passive"))
      (node (ref "R102") (pin "1") (pintype "passive"))
      (node (ref "R131") (pin "1") (pintype "passive"))
      (node (ref "R50") (pin "1") (pintype "passive"))
      (node (ref "R56") (pin "1") (pintype "passive"))
      (node (ref "R62") (pin "1") (pintype "passive"))
      (node (ref "R73") (pin "2") (pintype "passive"))
    )
    (net (code "50") (name "Net-(D9-IO1)") (class "Default")
      (node (ref "C62") (pin "2") (pinfunction "2_2") (pintype "passive"))
      (node (ref "D9") (pin "1") (pinfunction "IO1_1") (pintype "passive"))
      (node (ref "D9") (pin "2") (pinfunction "IO2_2") (pintype "passive"))
      (node (ref "J5") (pin "1") (pinfunction "VCC_1") (pintype "power_in"))
      (node (ref "R71") (pin "1") (pintype "passive"))
      (node (ref "R72") (pin "1") (pintype "passive"))
    )
    (net (code "51") (name "Net-(IC5-3V3OUT)") (class "Default")
      (node (ref "C30") (pin "2") (pinfunction "2_2") (pintype "passive"))
      (node (ref "IC5") (pin "16") (pinfunction "3V3OUT_16") (pintype "power_in"))
    )
    (net (code "52") (name "Net-(IC5-RXD)") (class "Default")
      (node (ref "IC5") (pin "2") (pinfunction "RXD_2") (pintype "input"))
      (node (ref "R41") (pin "1") (pintype "passive"))
    )
    (net (code "53") (name "Net-(IC5-TXD)") (class "Default")
      (node (ref "IC5") (pin "30") (pinfunction "TXD_30") (pintype "output"))
      (node (ref "R20") (pin "1") (pintype "passive"))
    )
    (net (code "54") (name "Net-(IC7-CURRENT_MODE)") (class "Default")
      (node (ref "IC7") (pin "3") (pinfunction "CURRENT_MODE_3") (pintype "passive"))
      (node (ref "R54") (pin "2") (pintype "passive"))
    )
    (net (code "55") (name "Net-(IC7-DIR)") (class "Default")
      (node (ref "IC7") (pin "11") (pinfunction "DIR_11") (pintype "passive"))
      (node (ref "R53") (pin "1") (pintype "passive"))
    )
    (net (code "56") (name "Net-(IC7-ENn_CC)") (class "Default")
      (node (ref "IC7") (pin "29") (pinfunction "ENn_CC_29") (pintype "passive"))
      (node (ref "R62") (pin "2") (pintype "passive"))
    )
    (net (code "57") (name "Net-(IC7-PORT)") (class "Default")
      (node (ref "IC7") (pin "4") (pinfunction "PORT_4") (pintype "passive"))
      (node (ref "R55") (pin "2") (pintype "passive"))
    )
    (net (code "58") (name "Net-(IC7-VBUS_DET)") (class "Default")
      (node (ref "IC7") (pin "5") (pinfunction "VBUS_DET_5") (pintype "passive"))
      (node (ref "R51") (pin "1") (pintype "passive"))
    )
    (net (code "59") (name "Net-(IC16-EN)") (class "Default")
      (node (ref "IC16") (pin "3") (pinfunction "EN_3") (pintype "passive"))
      (node (ref "R102") (pin "2") (pintype "passive"))
      (node (ref "R47") (pin "1") (pintype "passive"))
      (node (ref "R49") (pin "2") (pintype "passive"))
    )
    (net (code "60") (name "Net-(IC16-ILIM)") (class "Default")
      (node (ref "IC16") (pin "5") (pinfunction "ILIM_5") (pintype "passive"))
      (node (ref "R50") (pin "2") (pintype "passive"))
    )
    (net (code "61") (name "Net-(IC16-OUT)") (class "Default")
      (node (ref "C31") (pin "2") (pinfunction "2_2") (pintype "passive"))
      (node (ref "IC16") (pin "6") (pinfunction "OUT_6") (pintype "passive"))
      (node (ref "L2") (pin "1") (pintype "passive"))
    )
    (net (code "62") (name "Net-(IC16-~{FLAG})") (class "Default")
      (node (ref "IC16") (pin "4") (pinfunction "~{FLAG}_4") (pintype "passive"))
      (node (ref "LED1") (pin "K") (pinfunction "K_K") (pintype "passive"))
    )
    (net (code "63") (name "Net-(J5-ID)") (class "Default")
      (node (ref "J5") (pin "4") (pinfunction "ID_4") (pintype "passive"))
      (node (ref "TP22") (pin "1") (pintype "passive"))
    )
    (net (code "64") (name "Net-(J9-VCC)") (class "Default")
      (node (ref "J9") (pin "1") (pinfunction "VCC_1") (pintype "power_in"))
      (node (ref "L3") (pin "1") (pintype "passive"))
    )
    (net (code "65") (name "Net-(J11-SBU2)") (class "Default")
      (node (ref "J11") (pin "B8") (pinfunction "SBU2_B8") (pintype "passive"))
      (node (ref "TP19") (pin "1") (pintype "passive"))
    )
    (net (code "66") (name "Net-(LED1-PadA)") (class "Default")
      (node (ref "LED1") (pin "A") (pinfunction "A_A") (pintype "passive"))
      (node (ref "R43") (pin "1") (pintype "passive"))
    )
    (net (code "67") (name "Net-(Q1-D)") (class "Default")
      (node (ref "Q1") (pin "3") (pinfunction "D_3") (pintype "passive"))
      (node (ref "R49") (pin "1") (pintype "passive"))
    )
    (net (code "68") (name "Net-(Q2-G)") (class "Default")
      (node (ref "Q2") (pin "1") (pinfunction "G_1") (pintype "passive"))
      (node (ref "R72") (pin "2") (pintype "passive"))
      (node (ref "R73") (pin "1") (pintype "passive"))
    )
    (net (code "69") (name "SHIELD") (class "Default")
      (node (ref "J9") (pin "S") (pinfunction "SHIELD_S") (pintype "passive"))
    )
    (net (code "70") (name "SHIELD_OTG") (class "Default")
      (node (ref "J5") (pin "S") (pinfunction "SHIELD_S") (pintype "passive"))
      (node (ref "L7") (pin "1") (pintype "passive"))
    )
    (net (code "71") (name "USBC_VBUS") (class "Default")
      (node (ref "C35") (pin "2") (pinfunction "2_2") (pintype "passive"))
      (node (ref "J11") (pin "A4") (pinfunction "VBUS_A4") (pintype "passive"))
      (node (ref "J11") (pin "A9") (pinfunction "VBUS_A9") (pintype "passive"))
      (node (ref "J11") (pin "B4") (pinfunction "VBUS_B4") (pintype "passive"))
      (node (ref "J11") (pin "B9") (pinfunction "VBUS_B9") (pintype "passive"))
      (node (ref "L2") (pin "2") (pintype "passive"))
      (node (ref "R131") (pin "2") (pintype "passive"))
      (node (ref "R42") (pin "2") (pintype "passive"))
      (node (ref "R51") (pin "2") (pintype "passive"))
    )
    (net (code "72") (name "unconnected-(IC5-CBUS0-Pad22)") (class "Default")
      (node (ref "IC5") (pin "22") (pinfunction "CBUS0_22") (pintype "bidirectional+no_connect"))
    )
    (net (code "73") (name "unconnected-(IC5-CBUS1-Pad21)") (class "Default")
      (node (ref "IC5") (pin "21") (pinfunction "CBUS1_21") (pintype "bidirectional+no_connect"))
    )
    (net (code "74") (name "unconnected-(IC5-CBUS2-Pad10)") (class "Default")
      (node (ref "IC5") (pin "10") (pinfunction "CBUS2_10") (pintype "bidirectional+no_connect"))
    )
    (net (code "75") (name "unconnected-(IC5-CBUS3-Pad11)") (class "Default")
      (node (ref "IC5") (pin "11") (pinfunction "CBUS3_11") (pintype "bidirectional+no_connect"))
    )
    (net (code "76") (name "unconnected-(IC5-CBUS4-Pad9)") (class "Default")
      (node (ref "IC5") (pin "9") (pinfunction "CBUS4_9") (pintype "bidirectional+no_connect"))
    )
    (net (code "77") (name "unconnected-(IC5-CTS#-Pad8)") (class "Default")
      (node (ref "IC5") (pin "8") (pinfunction "CTS#_8") (pintype "input+no_connect"))
    )
    (net (code "78") (name "unconnected-(IC5-DCD#-Pad7)") (class "Default")
      (node (ref "IC5") (pin "7") (pinfunction "DCD#_7") (pintype "input+no_connect"))
    )
    (net (code "79") (name "unconnected-(IC5-DSR#-Pad6)") (class "Default")
      (node (ref "IC5") (pin "6") (pinfunction "DSR#_6") (pintype "input+no_connect"))
    )
    (net (code "80") (name "unconnected-(IC5-DTR#-Pad31)") (class "Default")
      (node (ref "IC5") (pin "31") (pinfunction "DTR#_31") (pintype "output+no_connect"))
    )
    (net (code "81") (name "unconnected-(IC5-OSCI-Pad27)") (class "Default")
      (node (ref "IC5") (pin "27") (pinfunction "OSCI_27") (pintype "input+no_connect"))
    )
    (net (code "82") (name "unconnected-(IC5-OSCO-Pad28)") (class "Default")
      (node (ref "IC5") (pin "28") (pinfunction "OSCO_28") (pintype "output+no_connect"))
    )
    (net (code "83") (name "unconnected-(IC5-RESET#-Pad18)") (class "Default")
      (node (ref "IC5") (pin "18") (pinfunction "RESET#_18") (pintype "input+no_connect"))
    )
    (net (code "84") (name "unconnected-(IC5-RI#-Pad3)") (class "Default")
      (node (ref "IC5") (pin "3") (pinfunction "RI#_3") (pintype "input+no_connect"))
    )
    (net (code "85") (name "unconnected-(IC5-RTS#-Pad32)") (class "Default")
      (node (ref "IC5") (pin "32") (pinfunction "RTS#_32") (pintype "output+no_connect"))
    )
    (net (code "86") (name "unconnected-(J9-ID-Pad4)") (class "Default")
      (node (ref "J9") (pin "4") (pinfunction "ID_4") (pintype "passive+no_connect"))
    )
    (net (code "87") (name "unconnected-(J11-SBU1-PadA8)") (class "Default")
      (node (ref "J11") (pin "A8") (pinfunction "SBU1_A8") (pintype "passive"))
    )
  )
)
